# Clock_Distribution.net
KiCad netlist of a schematic drawn in Altium Designer
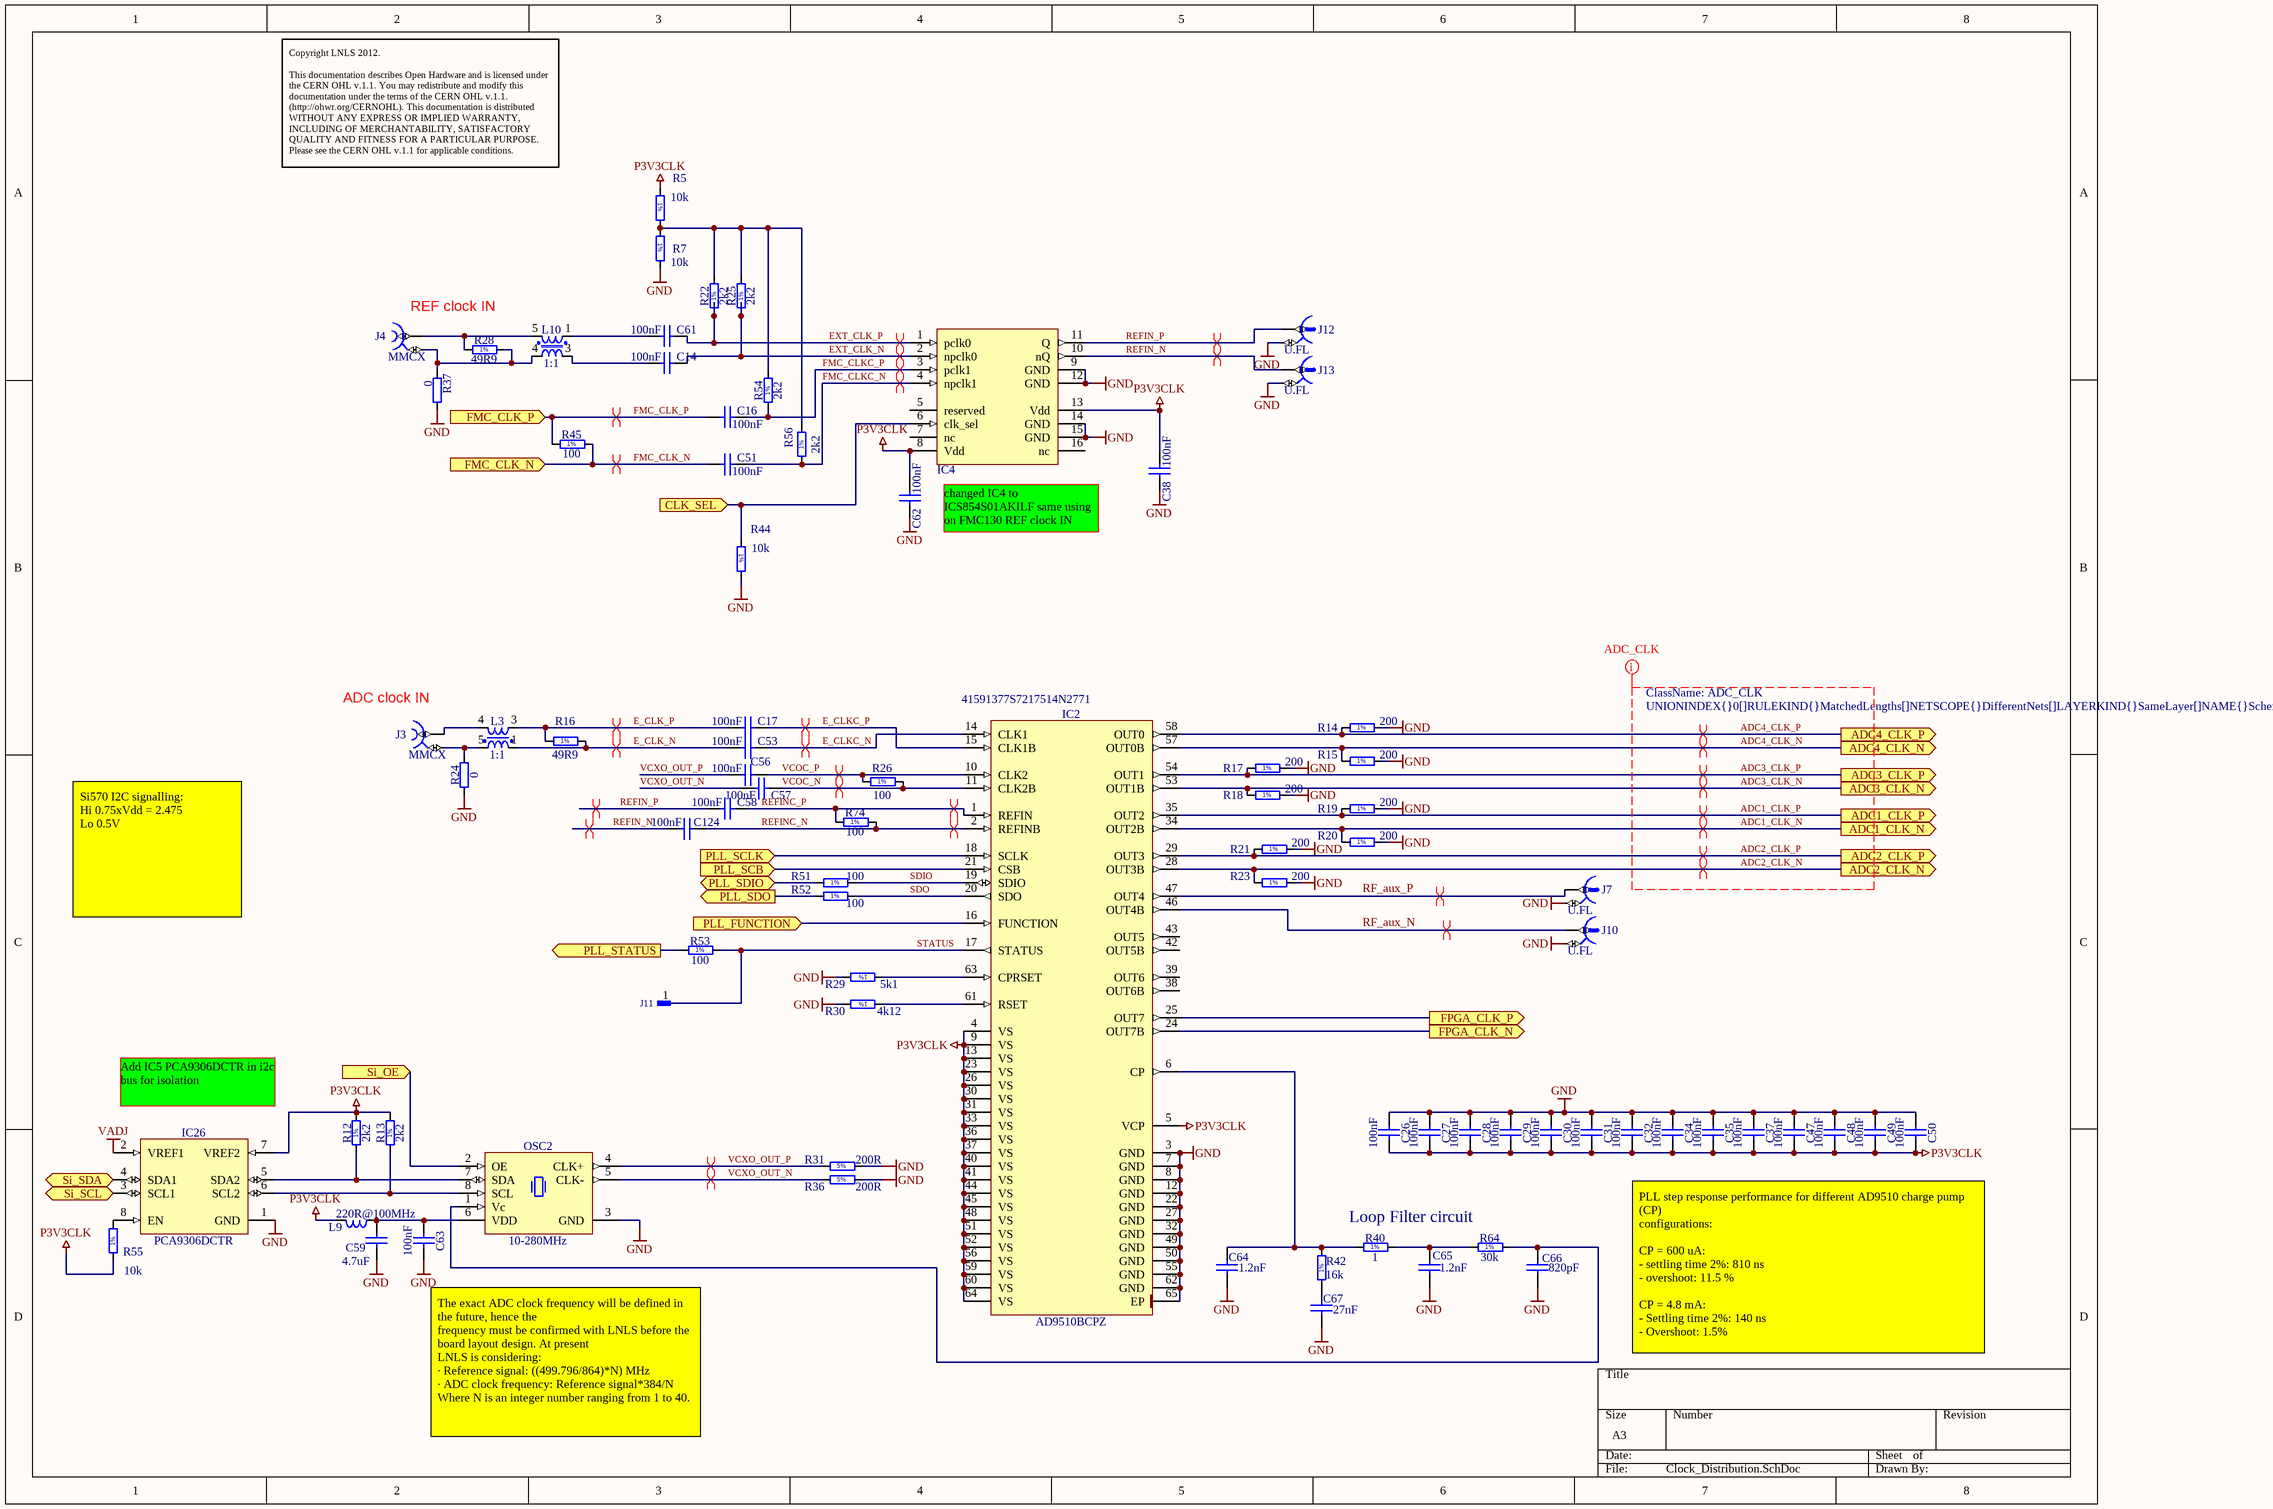
[diagram p0: Clock_Distribution.SchDoc]

(export (version "E")
  (design (tool "Eeschema 10.0.6"))
  (components
    (comp (ref "C14")
      (value "100nF")
      (footprint "CAPC0603X33N")
      (description "Non-polarised capacitor")
      (fields
        (field (name "PART NUMBER") "CC0201_100NF_6.3V_10%_X5R")
        (field (name "VOLTAGE") "6.3V")
        (field (name "AUTHOR") "CERN DEM JLC")
      )
      (libsource (lib "Capacitors") (part "Capacitor - non polarized"))
    )
    (comp (ref "C16")
      (value "100nF")
      (footprint "CAPC0603X33N")
      (description "Non-polarised capacitor")
      (fields
        (field (name "PART NUMBER") "CC0201_100NF_6.3V_10%_X5R")
        (field (name "VOLTAGE") "6.3V")
        (field (name "AUTHOR") "CERN DEM JLC")
      )
      (libsource (lib "Capacitors") (part "Capacitor - non polarized"))
    )
    (comp (ref "C17")
      (value "100nF")
      (footprint "CAPC0603X33N")
      (description "Non-polarised capacitor")
      (fields
        (field (name "PART NUMBER") "CC0201_100NF_6.3V_10%_X5R")
        (field (name "VOLTAGE") "6.3V")
        (field (name "AUTHOR") "CERN DEM JLC")
      )
      (libsource (lib "Capacitors") (part "Capacitor - non polarized"))
    )
    (comp (ref "C26")
      (value "100nF")
      (footprint "CAPC0603X33N")
      (description "Non-polarised capacitor")
      (fields
        (field (name "PART NUMBER") "CC0201_100NF_6.3V_10%_X5R")
        (field (name "VOLTAGE") "6.3V")
        (field (name "AUTHOR") "CERN DEM JLC")
      )
      (libsource (lib "Capacitors") (part "Capacitor - non polarized"))
    )
    (comp (ref "C27")
      (value "100nF")
      (footprint "CAPC0603X33N")
      (description "Non-polarised capacitor")
      (fields
        (field (name "PART NUMBER") "CC0201_100NF_6.3V_10%_X5R")
        (field (name "VOLTAGE") "6.3V")
        (field (name "AUTHOR") "CERN DEM JLC")
      )
      (libsource (lib "Capacitors") (part "Capacitor - non polarized"))
    )
    (comp (ref "C28")
      (value "100nF")
      (footprint "CAPC0603X33N")
      (description "Non-polarised capacitor")
      (fields
        (field (name "PART NUMBER") "CC0201_100NF_6.3V_10%_X5R")
        (field (name "VOLTAGE") "6.3V")
        (field (name "AUTHOR") "CERN DEM JLC")
      )
      (libsource (lib "Capacitors") (part "Capacitor - non polarized"))
    )
    (comp (ref "C29")
      (value "100nF")
      (footprint "CAPC0603X33N")
      (description "Non-polarised capacitor")
      (fields
        (field (name "PART NUMBER") "CC0201_100NF_6.3V_10%_X5R")
        (field (name "VOLTAGE") "6.3V")
        (field (name "AUTHOR") "CERN DEM JLC")
      )
      (libsource (lib "Capacitors") (part "Capacitor - non polarized"))
    )
    (comp (ref "C30")
      (value "100nF")
      (footprint "CAPC0603X33N")
      (description "Non-polarised capacitor")
      (fields
        (field (name "PART NUMBER") "CC0201_100NF_6.3V_10%_X5R")
        (field (name "VOLTAGE") "6.3V")
        (field (name "AUTHOR") "CERN DEM JLC")
      )
      (libsource (lib "Capacitors") (part "Capacitor - non polarized"))
    )
    (comp (ref "C31")
      (value "100nF")
      (footprint "CAPC0603X33N")
      (description "Non-polarised capacitor")
      (fields
        (field (name "PART NUMBER") "CC0201_100NF_6.3V_10%_X5R")
        (field (name "VOLTAGE") "6.3V")
        (field (name "AUTHOR") "CERN DEM JLC")
      )
      (libsource (lib "Capacitors") (part "Capacitor - non polarized"))
    )
    (comp (ref "C32")
      (value "100nF")
      (footprint "CAPC0603X33N")
      (description "Non-polarised capacitor")
      (fields
        (field (name "PART NUMBER") "CC0201_100NF_6.3V_10%_X5R")
        (field (name "VOLTAGE") "6.3V")
        (field (name "AUTHOR") "CERN DEM JLC")
      )
      (libsource (lib "Capacitors") (part "Capacitor - non polarized"))
    )
    (comp (ref "C34")
      (value "100nF")
      (footprint "CAPC0603X33N")
      (description "Non-polarised capacitor")
      (fields
        (field (name "PART NUMBER") "CC0201_100NF_6.3V_10%_X5R")
        (field (name "VOLTAGE") "6.3V")
        (field (name "AUTHOR") "CERN DEM JLC")
      )
      (libsource (lib "Capacitors") (part "Capacitor - non polarized"))
    )
    (comp (ref "C35")
      (value "100nF")
      (footprint "CAPC0603X33N")
      (description "Non-polarised capacitor")
      (fields
        (field (name "PART NUMBER") "CC0201_100NF_6.3V_10%_X5R")
        (field (name "VOLTAGE") "6.3V")
        (field (name "AUTHOR") "CERN DEM JLC")
      )
      (libsource (lib "Capacitors") (part "Capacitor - non polarized"))
    )
    (comp (ref "C37")
      (value "100nF")
      (footprint "CAPC0603X33N")
      (description "Non-polarised capacitor")
      (fields
        (field (name "PART NUMBER") "CC0201_100NF_6.3V_10%_X5R")
        (field (name "VOLTAGE") "6.3V")
        (field (name "AUTHOR") "CERN DEM JLC")
      )
      (libsource (lib "Capacitors") (part "Capacitor - non polarized"))
    )
    (comp (ref "C38")
      (value "100nF")
      (footprint "CAPC0603X33N")
      (description "Non-polarised capacitor")
      (fields
        (field (name "PART NUMBER") "CC0201_100NF_6.3V_10%_X5R")
        (field (name "VOLTAGE") "6.3V")
        (field (name "AUTHOR") "CERN DEM JLC")
      )
      (libsource (lib "Capacitors") (part "Capacitor - non polarized"))
    )
    (comp (ref "C47")
      (value "100nF")
      (footprint "CAPC0603X33N")
      (description "Non-polarised capacitor")
      (fields
        (field (name "PART NUMBER") "CC0201_100NF_6.3V_10%_X5R")
        (field (name "VOLTAGE") "6.3V")
        (field (name "AUTHOR") "CERN DEM JLC")
      )
      (libsource (lib "Capacitors") (part "Capacitor - non polarized"))
    )
    (comp (ref "C48")
      (value "100nF")
      (footprint "CAPC0603X33N")
      (description "Non-polarised capacitor")
      (fields
        (field (name "PART NUMBER") "CC0201_100NF_6.3V_10%_X5R")
        (field (name "VOLTAGE") "6.3V")
        (field (name "AUTHOR") "CERN DEM JLC")
      )
      (libsource (lib "Capacitors") (part "Capacitor - non polarized"))
    )
    (comp (ref "C49")
      (value "100nF")
      (footprint "CAPC0603X33N")
      (description "Non-polarised capacitor")
      (fields
        (field (name "PART NUMBER") "CC0201_100NF_6.3V_10%_X5R")
        (field (name "VOLTAGE") "6.3V")
        (field (name "AUTHOR") "CERN DEM JLC")
      )
      (libsource (lib "Capacitors") (part "Capacitor - non polarized"))
    )
    (comp (ref "C50")
      (value "100nF")
      (footprint "CAPC0603X33N")
      (description "Non-polarised capacitor")
      (fields
        (field (name "PART NUMBER") "CC0201_100NF_6.3V_10%_X5R")
        (field (name "VOLTAGE") "6.3V")
        (field (name "AUTHOR") "CERN DEM JLC")
      )
      (libsource (lib "Capacitors") (part "Capacitor - non polarized"))
    )
    (comp (ref "C51")
      (value "100nF")
      (footprint "CAPC0603X33N")
      (description "Non-polarised capacitor")
      (fields
        (field (name "PART NUMBER") "CC0201_100NF_6.3V_10%_X5R")
        (field (name "VOLTAGE") "6.3V")
        (field (name "AUTHOR") "CERN DEM JLC")
      )
      (libsource (lib "Capacitors") (part "Capacitor - non polarized"))
    )
    (comp (ref "C53")
      (value "100nF")
      (footprint "CAPC0603X33N")
      (description "Non-polarised capacitor")
      (fields
        (field (name "PART NUMBER") "CC0201_100NF_6.3V_10%_X5R")
        (field (name "VOLTAGE") "6.3V")
        (field (name "AUTHOR") "CERN DEM JLC")
      )
      (libsource (lib "Capacitors") (part "Capacitor - non polarized"))
    )
    (comp (ref "C56")
      (value "100nF")
      (footprint "CAPC0603X33N")
      (description "Non-polarised capacitor")
      (fields
        (field (name "PART NUMBER") "CC0201_100NF_6.3V_10%_X5R")
        (field (name "VOLTAGE") "6.3V")
        (field (name "AUTHOR") "CERN DEM JLC")
      )
      (libsource (lib "Capacitors") (part "Capacitor - non polarized"))
    )
    (comp (ref "C57")
      (value "100nF")
      (footprint "CAPC0603X33N")
      (description "Non-polarised capacitor")
      (fields
        (field (name "PART NUMBER") "CC0201_100NF_6.3V_10%_X5R")
        (field (name "VOLTAGE") "6.3V")
        (field (name "AUTHOR") "CERN DEM JLC")
      )
      (libsource (lib "Capacitors") (part "Capacitor - non polarized"))
    )
    (comp (ref "C58")
      (value "100nF")
      (footprint "CAPC0603X33N")
      (description "Non-polarised capacitor")
      (fields
        (field (name "PART NUMBER") "CC0201_100NF_6.3V_10%_X5R")
        (field (name "VOLTAGE") "6.3V")
        (field (name "AUTHOR") "CERN DEM JLC")
      )
      (libsource (lib "Capacitors") (part "Capacitor - non polarized"))
    )
    (comp (ref "C59")
      (value "4.7uF")
      (footprint "CAPC1608X90N")
      (description "Non-polarised capacitor")
      (fields
        (field (name "PART NUMBER") "CC0603_4.7UF_25V_10%_X5R")
        (field (name "VOLTAGE") "25V")
        (field (name "AUTHOR") "CERN DEM JLC")
      )
      (libsource (lib "Capacitors") (part "Capacitor - non polarized"))
    )
    (comp (ref "C61")
      (value "100nF")
      (footprint "CAPC0603X33N")
      (description "Non-polarised capacitor")
      (fields
        (field (name "PART NUMBER") "CC0201_100NF_6.3V_10%_X5R")
        (field (name "VOLTAGE") "6.3V")
        (field (name "AUTHOR") "CERN DEM JLC")
      )
      (libsource (lib "Capacitors") (part "Capacitor - non polarized"))
    )
    (comp (ref "C62")
      (value "100nF")
      (footprint "CAPC0603X33N")
      (description "Non-polarised capacitor")
      (fields
        (field (name "PART NUMBER") "CC0201_100NF_6.3V_10%_X5R")
        (field (name "VOLTAGE") "6.3V")
        (field (name "AUTHOR") "CERN DEM JLC")
      )
      (libsource (lib "Capacitors") (part "Capacitor - non polarized"))
    )
    (comp (ref "C63")
      (value "100nF")
      (footprint "CAPC0603X33N")
      (description "Non-polarised capacitor")
      (fields
        (field (name "PART NUMBER") "CC0201_100NF_6.3V_10%_X5R")
        (field (name "VOLTAGE") "6.3V")
        (field (name "AUTHOR") "CERN DEM JLC")
      )
      (libsource (lib "Capacitors") (part "Capacitor - non polarized"))
    )
    (comp (ref "C64")
      (value "1.2nF")
      (footprint "CAPC1608X87N")
      (description "Non-polarised capacitor")
      (fields
        (field (name "PART NUMBER") "CC0603_1.2NF_50V_10%_X7R")
        (field (name "VOLTAGE") "50V")
        (field (name "AUTHOR") "CERN DEM JLC")
      )
      (libsource (lib "Capacitors") (part "Capacitor - non polarized"))
    )
    (comp (ref "C65")
      (value "1.2nF")
      (footprint "CAPC1608X87N")
      (description "Non-polarised capacitor")
      (fields
        (field (name "PART NUMBER") "CC0603_1.2NF_50V_10%_X7R")
        (field (name "VOLTAGE") "50V")
        (field (name "AUTHOR") "CERN DEM JLC")
      )
      (libsource (lib "Capacitors") (part "Capacitor - non polarized"))
    )
    (comp (ref "C66")
      (value "820pF")
      (footprint "CAPC1608X87N")
      (description "Non-polarised capacitor")
      (fields
        (field (name "PART NUMBER") "CC0603_820PF_50V_10%_X7R")
        (field (name "VOLTAGE") "50V")
        (field (name "AUTHOR") "CERN DEM JLC")
      )
      (libsource (lib "Capacitors") (part "Capacitor - non polarized"))
    )
    (comp (ref "C67")
      (value "27nF")
      (footprint "CAPC1608X87N")
      (description "Non-polarised capacitor")
      (fields
        (field (name "PART NUMBER") "CC0603_27NF_25V_10%_X7R")
        (field (name "VOLTAGE") "25V")
        (field (name "AUTHOR") "CERN DEM JLC")
      )
      (libsource (lib "Capacitors") (part "Capacitor - non polarized"))
    )
    (comp (ref "C124")
      (value "100nF")
      (footprint "CAPC0603X33N")
      (description "Non-polarised capacitor")
      (fields
        (field (name "PART NUMBER") "CC0201_100NF_6.3V_10%_X5R")
        (field (name "VOLTAGE") "6.3V")
        (field (name "AUTHOR") "CERN DEM JLC")
      )
      (libsource (lib "Capacitors") (part "Capacitor - non polarized"))
    )
    (comp (ref "IC2")
      (value "AD9510BCPZ")
      (footprint "QFN50P900X900X100-65N-S485")
      (description "1.2 GHz Clock Distribution IC, PLL Core, Dividers, Delay Adjust, Eight Outputs")
      (fields
        (field (name "MANUFACTURER") "ANALOG DEVICES")
        (field (name "SUPPLIER PART NUMBER 1") "41591377S7217514N2771")
        (field (name "AUTHOR") "CERN DEM JLC")
      )
      (libsource (lib "ICs And Semiconductors") (part "AD9510"))
    )
    (comp (ref "IC4")
      (value "ICS854S01AKILF")
      (footprint "QFN50P300x300x100-17N-S140")
      (description "2:1 Differential-to-LVDS Multiplexer")
      (fields
        (field (name "MANUFACTURER") "INTEGRATED DEVICE TECHNOLOGY (IDT)")
        (field (name "AUTHOR") "LNLS DIG GBMB")
      )
      (libsource (lib "ICs And Semiconductors_LNLS") (part "ICS854S01l"))
    )
    (comp (ref "IC26")
      (value "PCA9306DCTR")
      (footprint "SOP65P400X130-8N")
      (description "Dual Bidirectional I2C Bus And SMBus Voltage-Level Translator")
      (fields (field (name "MANUFACTURER") "TEXAS INSTRUMENTS") (field (name "AUTHOR") "CERN DEM JLC"))
      (libsource (lib "ICs And Semiconductors") (part "PCA9306DC"))
    )
    (comp (ref "J3")
      (value "MMCX")
      (footprint "HUBER-SUHNER_85_MMCX-50-0-1/111_OH")
      (fields
        (field (name "PART NUMBER") "HUBER-SUHNER_85_MMCX-50-0-1/111_OH")
        (field (name "MANUFACTURER") "HUBER+SUHNER")
        (field (name "MANUFACTURER PART NUMBER") "85_MMCX-50-0-1/111_OH")
        (field (name "AUTHOR") "CERN DEM JLC")
      )
      (libsource (lib "Connectors") (part "Coax_1Female_1Shield"))
    )
    (comp (ref "J4")
      (value "MMCX")
      (footprint "HUBER-SUHNER_85_MMCX-50-0-1/111_OH")
      (fields
        (field (name "PART NUMBER") "HUBER-SUHNER_85_MMCX-50-0-1/111_OH")
        (field (name "MANUFACTURER") "HUBER+SUHNER")
        (field (name "MANUFACTURER PART NUMBER") "85_MMCX-50-0-1/111_OH")
        (field (name "AUTHOR") "CERN DEM JLC")
      )
      (libsource (lib "Connectors") (part "Coax_1Female_1Shield"))
    )
    (comp (ref "J7")
      (value "U.FL")
      (footprint "HIROSE_U.FL-R-SMT-1(10)")
      (fields
        (field (name "PART NUMBER") "HIROSE_U.FL-R-SMT-1(10)")
        (field (name "MANUFACTURER") "HIROSE (HRS)")
        (field (name "MANUFACTURER PART NUMBER") "U.FL-R-SMT-1(10)")
        (field (name "AUTHOR") "CERN DEM JLC")
      )
      (libsource (lib "Connectors") (part "Coax_1Male_1Shield"))
    )
    (comp (ref "J10")
      (value "U.FL")
      (footprint "HIROSE_U.FL-R-SMT-1(10)")
      (fields
        (field (name "PART NUMBER") "HIROSE_U.FL-R-SMT-1(10)")
        (field (name "MANUFACTURER") "HIROSE (HRS)")
        (field (name "MANUFACTURER PART NUMBER") "U.FL-R-SMT-1(10)")
        (field (name "AUTHOR") "CERN DEM JLC")
      )
      (libsource (lib "Connectors") (part "Coax_1Male_1Shield"))
    )
    (comp (ref "J11")
      (value "SMD Pad")
      (footprint "R400X300")
      (description "Single SMD Pad")
      (fields (field (name "PART NUMBER") "SMD_PAD_4X3MM") (field (name "AUTHOR") "CERN DEM JLC"))
      (libsource (lib "Eletro-mechanical") (part "Single SMD Pad"))
    )
    (comp (ref "J12")
      (value "U.FL")
      (footprint "HIROSE_U.FL-R-SMT-1(10)")
      (fields
        (field (name "PART NUMBER") "HIROSE_U.FL-R-SMT-1(10)")
        (field (name "MANUFACTURER") "HIROSE (HRS)")
        (field (name "MANUFACTURER PART NUMBER") "U.FL-R-SMT-1(10)")
        (field (name "AUTHOR") "CERN DEM JLC")
      )
      (libsource (lib "Connectors") (part "Coax_1Male_1Shield"))
    )
    (comp (ref "J13")
      (value "U.FL")
      (footprint "HIROSE_U.FL-R-SMT-1(10)")
      (fields
        (field (name "PART NUMBER") "HIROSE_U.FL-R-SMT-1(10)")
        (field (name "MANUFACTURER") "HIROSE (HRS)")
        (field (name "MANUFACTURER PART NUMBER") "U.FL-R-SMT-1(10)")
        (field (name "AUTHOR") "CERN DEM JLC")
      )
      (libsource (lib "Connectors") (part "Coax_1Male_1Shield"))
    )
    (comp (ref "L3")
      (value "1:1")
      (footprint "XFMR_MA-COM_SM-22 (H260)")
      (description "MA-COM E-Serie RF 1:1 Transmission Line Ttransformer 4.5-3000MHz")
      (fields
        (field (name "PART NUMBER") "XFMR_MA-COM_MABA-007159-000000")
        (field (name "MANUFACTURER") "MA-COM TECHNOLOGY")
        (field (name "AUTHOR") "CERN DEM JLC")
      )
      (libsource (lib "Inductors & Transformers") (part "XFMR_MA-COM_MABA-007159-000000"))
    )
    (comp (ref "L9")
      (value "220R@100MHz")
      (footprint "INDC1005X55N")
      (description "Inductor")
      (fields
        (field (name "PART NUMBER") "IND0402_MURATA_BLM15HB221SN1")
        (field (name "POWER") "250mA")
        (field (name "AUTHOR") "CERN DEM JLC")
      )
      (libsource (lib "Inductors & Transformers") (part "Inductor"))
    )
    (comp (ref "L10")
      (value "1:1")
      (footprint "XFMR_MA-COM_SM-22 (H260)")
      (description "MA-COM E-Serie RF 1:1 Transmission Line Ttransformer 4.5-3000MHz")
      (fields
        (field (name "PART NUMBER") "XFMR_MA-COM_MABA-007159-000000")
        (field (name "MANUFACTURER") "MA-COM TECHNOLOGY")
        (field (name "AUTHOR") "CERN DEM JLC")
      )
      (libsource (lib "") (part "XFMR_MA-COM_MABA-007159-000000_1"))
    )
    (comp (ref "OSC2")
      (value "10-280MHz")
      (footprint "OSC_SILICON-LAB_SI571")
      (description "Any-Rate I2C Programmable XO Oscillator Si571 Serie")
      (fields
        (field (name "PART NUMBER") "OSC_10-280MHZ_SILICON-LAB_Si571AJC000337DG")
        (field (name "MANUFACTURER") "SILICON LABS")
        (field (name "AUTHOR") "CERN DEM JLC")
      )
      (libsource (lib "ICs And Semiconductors") (part "Oscillator SILICON-LAB_Si571"))
    )
    (comp (ref "R5")
      (value "10k")
      (footprint "RESC1005X40N")
      (description "Resistor - 1%")
      (fields
        (field (name "PART NUMBER") "R0402_10K_1%_0.0625W_100PPM")
        (field (name "POWER") "0.0625W")
        (field (name "AUTHOR") "CERN DEM JLC")
      )
      (libsource (lib "Resistors") (part "Resistor - 1%"))
    )
    (comp (ref "R7")
      (value "10k")
      (footprint "RESC1005X40N")
      (description "Resistor - 1%")
      (fields
        (field (name "PART NUMBER") "R0402_10K_1%_0.0625W_100PPM")
        (field (name "POWER") "0.0625W")
        (field (name "AUTHOR") "CERN DEM JLC")
      )
      (libsource (lib "Resistors") (part "Resistor - 1%"))
    )
    (comp (ref "R12")
      (value "2k2")
      (footprint "RESC1005X40N")
      (description "Resistor - 1%")
      (fields
        (field (name "PART NUMBER") "R0402_2K2_1%_0.0625W_100PPM")
        (field (name "POWER") "0.0625W")
        (field (name "AUTHOR") "CERN DEM JLC")
      )
      (libsource (lib "Resistors") (part "Resistor - 1%"))
    )
    (comp (ref "R13")
      (value "2k2")
      (footprint "RESC1005X40N")
      (description "Resistor - 1%")
      (fields
        (field (name "PART NUMBER") "R0402_2K2_1%_0.0625W_100PPM")
        (field (name "POWER") "0.0625W")
        (field (name "AUTHOR") "CERN DEM JLC")
      )
      (libsource (lib "Resistors") (part "Resistor - 1%"))
    )
    (comp (ref "R14")
      (value "200")
      (footprint "RESC1005X40N")
      (description "Resistor - 1%")
      (fields
        (field (name "PART NUMBER") "R0402_200R_1%_0.0625W_100PPM")
        (field (name "POWER") "0.0625W")
        (field (name "AUTHOR") "CERN DEM JLC")
      )
      (libsource (lib "Resistors") (part "Resistor - 1%"))
    )
    (comp (ref "R15")
      (value "200")
      (footprint "RESC1005X40N")
      (description "Resistor - 1%")
      (fields
        (field (name "PART NUMBER") "R0402_200R_1%_0.0625W_100PPM")
        (field (name "POWER") "0.0625W")
        (field (name "AUTHOR") "CERN DEM JLC")
      )
      (libsource (lib "Resistors") (part "Resistor - 1%"))
    )
    (comp (ref "R16")
      (value "49R9")
      (footprint "RESC1005X40N")
      (description "Resistor - 1%")
      (fields
        (field (name "PART NUMBER") "R0402_49R9_1%_0.0625W_100PPM")
        (field (name "POWER") "0.0625W")
        (field (name "AUTHOR") "CERN DEM JLC")
      )
      (libsource (lib "Resistors") (part "Resistor - 1%"))
    )
    (comp (ref "R17")
      (value "200")
      (footprint "RESC1005X40N")
      (description "Resistor - 1%")
      (fields
        (field (name "PART NUMBER") "R0402_200R_1%_0.0625W_100PPM")
        (field (name "POWER") "0.0625W")
        (field (name "AUTHOR") "CERN DEM JLC")
      )
      (libsource (lib "Resistors") (part "Resistor - 1%"))
    )
    (comp (ref "R18")
      (value "200")
      (footprint "RESC1005X40N")
      (description "Resistor - 1%")
      (fields
        (field (name "PART NUMBER") "R0402_200R_1%_0.0625W_100PPM")
        (field (name "POWER") "0.0625W")
        (field (name "AUTHOR") "CERN DEM JLC")
      )
      (libsource (lib "Resistors") (part "Resistor - 1%"))
    )
    (comp (ref "R19")
      (value "200")
      (footprint "RESC1005X40N")
      (description "Resistor - 1%")
      (fields
        (field (name "PART NUMBER") "R0402_200R_1%_0.0625W_100PPM")
        (field (name "POWER") "0.0625W")
        (field (name "AUTHOR") "CERN DEM JLC")
      )
      (libsource (lib "Resistors") (part "Resistor - 1%"))
    )
    (comp (ref "R20")
      (value "200")
      (footprint "RESC1005X40N")
      (description "Resistor - 1%")
      (fields
        (field (name "PART NUMBER") "R0402_200R_1%_0.0625W_100PPM")
        (field (name "POWER") "0.0625W")
        (field (name "AUTHOR") "CERN DEM JLC")
      )
      (libsource (lib "Resistors") (part "Resistor - 1%"))
    )
    (comp (ref "R21")
      (value "200")
      (footprint "RESC1005X40N")
      (description "Resistor - 1%")
      (fields
        (field (name "PART NUMBER") "R0402_200R_1%_0.0625W_100PPM")
        (field (name "POWER") "0.0625W")
        (field (name "AUTHOR") "CERN DEM JLC")
      )
      (libsource (lib "Resistors") (part "Resistor - 1%"))
    )
    (comp (ref "R22")
      (value "2k2")
      (footprint "RESC1005X40N")
      (description "Resistor - 1%")
      (fields
        (field (name "PART NUMBER") "R0402_2K2_1%_0.0625W_100PPM")
        (field (name "POWER") "0.0625W")
        (field (name "AUTHOR") "CERN DEM JLC")
      )
      (libsource (lib "Resistors") (part "Resistor - 1%"))
    )
    (comp (ref "R23")
      (value "200")
      (footprint "RESC1005X40N")
      (description "Resistor - 1%")
      (fields
        (field (name "PART NUMBER") "R0402_200R_1%_0.0625W_100PPM")
        (field (name "POWER") "0.0625W")
        (field (name "AUTHOR") "CERN DEM JLC")
      )
      (libsource (lib "Resistors") (part "Resistor - 1%"))
    )
    (comp (ref "R24")
      (value "0")
      (footprint "RESC0603X28N")
      (description "Resistor")
      (fields
        (field (name "PART NUMBER") "R0201_0R_JUMPER")
        (field (name "MANUFACTURER") "GENERIC")
        (field (name "AUTHOR") "CERN DEM JLC")
      )
      (libsource (lib "Resistors") (part "Resistor"))
    )
    (comp (ref "R25")
      (value "2k2")
      (footprint "RESC1005X40N")
      (description "Resistor - 1%")
      (fields
        (field (name "PART NUMBER") "R0402_2K2_1%_0.0625W_100PPM")
        (field (name "POWER") "0.0625W")
        (field (name "AUTHOR") "CERN DEM JLC")
      )
      (libsource (lib "Resistors") (part "Resistor - 1%"))
    )
    (comp (ref "R26")
      (value "100")
      (footprint "RESC1005X40N")
      (description "Resistor - 1%")
      (fields
        (field (name "PART NUMBER") "R0402_100R_1%_0.0625W_100PPM")
        (field (name "POWER") "0.0625W")
        (field (name "AUTHOR") "CERN DEM JLC")
      )
      (libsource (lib "Resistors") (part "Resistor - 1%"))
    )
    (comp (ref "R28")
      (value "49R9")
      (footprint "RESC1005X40N")
      (description "Resistor - 1%")
      (fields
        (field (name "PART NUMBER") "R0402_49R9_1%_0.0625W_100PPM")
        (field (name "POWER") "0.0625W")
        (field (name "AUTHOR") "CERN DEM JLC")
      )
      (libsource (lib "Resistors") (part "Resistor - 1%"))
    )
    (comp (ref "R29")
      (value "5k1")
      (footprint "RESC1005X40N")
      (description "Resistor - 1%")
      (fields
        (field (name "PART NUMBER") "R0402_5K1_1%_0.0625W_100PPM")
        (field (name "POWER") "0.0625W")
        (field (name "AUTHOR") "CERN DEM JLC")
      )
      (libsource (lib "Resistors") (part "Resistor - 1%"))
    )
    (comp (ref "R30")
      (value "4k12")
      (footprint "RESC1005X40N")
      (description "Resistor - 1%")
      (fields
        (field (name "PART NUMBER") "R0402_4K12_1%_0.0625W_100PPM")
        (field (name "POWER") "0.0625W")
        (field (name "AUTHOR") "CERN DEM JLC")
      )
      (libsource (lib "Resistors") (part "Resistor - 1%"))
    )
    (comp (ref "R31")
      (value "200R")
      (footprint "RESC1005X40N")
      (description "Resistor - 5%")
      (fields
        (field (name "PART NUMBER") "R0402_200R_5%_0.0625W_100PPM")
        (field (name "TOLERANCE") "5%")
        (field (name "AUTHOR") "CERN DEM JLC")
      )
      (libsource (lib "Resistors") (part "Resistor - 5%"))
    )
    (comp (ref "R36")
      (value "200R")
      (footprint "RESC1005X40N")
      (description "Resistor - 5%")
      (fields
        (field (name "PART NUMBER") "R0402_200R_5%_0.0625W_100PPM")
        (field (name "TOLERANCE") "5%")
        (field (name "AUTHOR") "CERN DEM JLC")
      )
      (libsource (lib "Resistors") (part "Resistor - 5%"))
    )
    (comp (ref "R37")
      (value "0")
      (footprint "RESC0603X28N")
      (description "Resistor")
      (fields
        (field (name "PART NUMBER") "R0201_0R_JUMPER")
        (field (name "MANUFACTURER") "GENERIC")
        (field (name "AUTHOR") "CERN DEM JLC")
      )
      (libsource (lib "Resistors") (part "Resistor"))
    )
    (comp (ref "R40")
      (value "1")
      (footprint "RESC1005X40N")
      (description "Resistor - 1%")
      (fields
        (field (name "PART NUMBER") "R0402_1R_1%_0.0625W_200PPM")
        (field (name "POWER") "0.0625W")
        (field (name "AUTHOR") "CERN DEM JLC")
      )
      (libsource (lib "Resistors") (part "Resistor - 1%"))
    )
    (comp (ref "R42")
      (value "16k")
      (footprint "RESC1608X55N")
      (description "Resistor - 1%")
      (fields
        (field (name "PART NUMBER") "R0603_16K_1%_0.1W_100PPM")
        (field (name "POWER") "0.1W")
        (field (name "AUTHOR") "CERN DEM JLC")
      )
      (libsource (lib "Resistors") (part "Resistor - 1%"))
    )
    (comp (ref "R44")
      (value "10k")
      (footprint "RESC1005X40N")
      (description "Resistor - 1%")
      (fields
        (field (name "PART NUMBER") "R0402_10K_1%_0.0625W_100PPM")
        (field (name "POWER") "0.0625W")
        (field (name "AUTHOR") "CERN DEM JLC")
      )
      (libsource (lib "Resistors") (part "Resistor - 1%"))
    )
    (comp (ref "R45")
      (value "100")
      (footprint "RESC1005X40N")
      (description "Resistor - 1%")
      (fields
        (field (name "PART NUMBER") "R0402_100R_1%_0.0625W_100PPM")
        (field (name "POWER") "0.0625W")
        (field (name "AUTHOR") "CERN DEM JLC")
      )
      (libsource (lib "Resistors") (part "Resistor - 1%"))
    )
    (comp (ref "R51")
      (value "100")
      (footprint "RESC1005X40N")
      (description "Resistor - 1%")
      (fields
        (field (name "PART NUMBER") "R0402_100R_1%_0.0625W_100PPM")
        (field (name "POWER") "0.0625W")
        (field (name "AUTHOR") "CERN DEM JLC")
      )
      (libsource (lib "Resistors") (part "Resistor - 1%"))
    )
    (comp (ref "R52")
      (value "100")
      (footprint "RESC1005X40N")
      (description "Resistor - 1%")
      (fields
        (field (name "PART NUMBER") "R0402_100R_1%_0.0625W_100PPM")
        (field (name "POWER") "0.0625W")
        (field (name "AUTHOR") "CERN DEM JLC")
      )
      (libsource (lib "Resistors") (part "Resistor - 1%"))
    )
    (comp (ref "R53")
      (value "100")
      (footprint "RESC1005X40N")
      (description "Resistor - 1%")
      (fields
        (field (name "PART NUMBER") "R0402_100R_1%_0.0625W_100PPM")
        (field (name "POWER") "0.0625W")
        (field (name "AUTHOR") "CERN DEM JLC")
      )
      (libsource (lib "Resistors") (part "Resistor - 1%"))
    )
    (comp (ref "R54")
      (value "2k2")
      (footprint "RESC1005X40N")
      (description "Resistor - 1%")
      (fields
        (field (name "PART NUMBER") "R0402_2K2_1%_0.0625W_100PPM")
        (field (name "POWER") "0.0625W")
        (field (name "AUTHOR") "CERN DEM JLC")
      )
      (libsource (lib "Resistors") (part "Resistor - 1%"))
    )
    (comp (ref "R55")
      (value "10k")
      (footprint "RESC1005X40N")
      (description "Resistor - 1%")
      (fields
        (field (name "PART NUMBER") "R0402_10K_1%_0.0625W_100PPM")
        (field (name "POWER") "0.0625W")
        (field (name "AUTHOR") "CERN DEM JLC")
      )
      (libsource (lib "Resistors") (part "Resistor - 1%"))
    )
    (comp (ref "R56")
      (value "2k2")
      (footprint "RESC1005X40N")
      (description "Resistor - 1%")
      (fields
        (field (name "PART NUMBER") "R0402_2K2_1%_0.0625W_100PPM")
        (field (name "POWER") "0.0625W")
        (field (name "AUTHOR") "CERN DEM JLC")
      )
      (libsource (lib "Resistors") (part "Resistor - 1%"))
    )
    (comp (ref "R64")
      (value "30k")
      (footprint "RESC1608X55N")
      (description "Resistor - 1%")
      (fields
        (field (name "PART NUMBER") "R0603_30K_1%_0.1W_100PPM")
        (field (name "POWER") "0.1W")
        (field (name "AUTHOR") "CERN DEM JLC")
      )
      (libsource (lib "Resistors") (part "Resistor - 1%"))
    )
    (comp (ref "R74")
      (value "100")
      (footprint "RESC1005X40N")
      (description "Resistor - 1%")
      (fields
        (field (name "PART NUMBER") "R0402_100R_1%_0.0625W_100PPM")
        (field (name "POWER") "0.0625W")
        (field (name "AUTHOR") "CERN DEM JLC")
      )
      (libsource (lib "Resistors") (part "Resistor - 1%"))
    )
  )
  (nets
    (net (code "1") (name "/ADC1_CLK_N") (class "Default")
      (node (ref "IC2") (pin "34") (pinfunction "OUT2B_34") (pintype "output"))
      (node (ref "R20") (pin "1") (pinfunction "1_1") (pintype "passive"))
    )
    (net (code "2") (name "/ADC1_CLK_P") (class "Default")
      (node (ref "IC2") (pin "35") (pinfunction "OUT2_35") (pintype "output"))
      (node (ref "R19") (pin "1") (pinfunction "1_1") (pintype "passive"))
    )
    (net (code "3") (name "/ADC2_CLK_N") (class "Default")
      (node (ref "IC2") (pin "28") (pinfunction "OUT3B_28") (pintype "output"))
      (node (ref "R23") (pin "1") (pinfunction "1_1") (pintype "passive"))
    )
    (net (code "4") (name "/ADC2_CLK_P") (class "Default")
      (node (ref "IC2") (pin "29") (pinfunction "OUT3_29") (pintype "output"))
      (node (ref "R21") (pin "1") (pinfunction "1_1") (pintype "passive"))
    )
    (net (code "5") (name "/ADC3_CLK_N") (class "Default")
      (node (ref "IC2") (pin "53") (pinfunction "OUT1B_53") (pintype "output"))
      (node (ref "R18") (pin "1") (pinfunction "1_1") (pintype "passive"))
    )
    (net (code "6") (name "/ADC3_CLK_P") (class "Default")
      (node (ref "IC2") (pin "54") (pinfunction "OUT1_54") (pintype "output"))
      (node (ref "R17") (pin "1") (pinfunction "1_1") (pintype "passive"))
    )
    (net (code "7") (name "/ADC4_CLK_N") (class "Default")
      (node (ref "IC2") (pin "57") (pinfunction "OUT0B_57") (pintype "output"))
      (node (ref "R15") (pin "1") (pinfunction "1_1") (pintype "passive"))
    )
    (net (code "8") (name "/ADC4_CLK_P") (class "Default")
      (node (ref "IC2") (pin "58") (pinfunction "OUT0_58") (pintype "output"))
      (node (ref "R14") (pin "1") (pinfunction "1_1") (pintype "passive"))
    )
    (net (code "9") (name "/CLK_SEL") (class "Default")
      (node (ref "IC4") (pin "6") (pinfunction "clk_sel_6") (pintype "input"))
      (node (ref "R44") (pin "1") (pinfunction "1_1") (pintype "passive"))
    )
    (net (code "10") (name "/EXT_CLK_N") (class "Default")
      (node (ref "C14") (pin "1") (pinfunction "1_1") (pintype "passive"))
      (node (ref "IC4") (pin "2") (pinfunction "npclk0_2") (pintype "input"))
      (node (ref "R25") (pin "1") (pinfunction "1_1") (pintype "passive"))
    )
    (net (code "11") (name "/EXT_CLK_P") (class "Default")
      (node (ref "C61") (pin "1") (pinfunction "1_1") (pintype "passive"))
      (node (ref "IC4") (pin "1") (pinfunction "pclk0_1") (pintype "input"))
      (node (ref "R22") (pin "1") (pinfunction "1_1") (pintype "passive"))
    )
    (net (code "12") (name "/E_CLKC_N") (class "Default")
      (node (ref "C53") (pin "1") (pinfunction "1_1") (pintype "passive"))
      (node (ref "IC2") (pin "14") (pinfunction "CLK1_14") (pintype "input"))
    )
    (net (code "13") (name "/E_CLKC_P") (class "Default")
      (node (ref "C17") (pin "1") (pinfunction "1_1") (pintype "passive"))
      (node (ref "IC2") (pin "15") (pinfunction "CLK1B_15") (pintype "input"))
    )
    (net (code "14") (name "/E_CLK_N") (class "Default")
      (node (ref "C53") (pin "2") (pinfunction "2_2") (pintype "passive"))
      (node (ref "L3") (pin "1") (pinfunction "1_1") (pintype "passive"))
      (node (ref "R16") (pin "2") (pinfunction "2_2") (pintype "passive"))
    )
    (net (code "15") (name "/E_CLK_P") (class "Default")
      (node (ref "C17") (pin "2") (pinfunction "2_2") (pintype "passive"))
      (node (ref "L3") (pin "3") (pinfunction "3_3") (pintype "passive"))
      (node (ref "R16") (pin "1") (pinfunction "1_1") (pintype "passive"))
    )
    (net (code "16") (name "/FMC_CLKC_N") (class "Default")
      (node (ref "C51") (pin "1") (pinfunction "1_1") (pintype "passive"))
      (node (ref "IC4") (pin "4") (pinfunction "npclk1_4") (pintype "input"))
      (node (ref "R56") (pin "1") (pinfunction "1_1") (pintype "passive"))
    )
    (net (code "17") (name "/FMC_CLKC_P") (class "Default")
      (node (ref "C16") (pin "1") (pinfunction "1_1") (pintype "passive"))
      (node (ref "IC4") (pin "3") (pinfunction "pclk1_3") (pintype "input"))
      (node (ref "R54") (pin "1") (pinfunction "1_1") (pintype "passive"))
    )
    (net (code "18") (name "/FMC_CLK_N") (class "Default")
      (node (ref "C51") (pin "2") (pinfunction "2_2") (pintype "passive"))
      (node (ref "R45") (pin "2") (pinfunction "2_2") (pintype "passive"))
    )
    (net (code "19") (name "/FMC_CLK_P") (class "Default")
      (node (ref "C16") (pin "2") (pinfunction "2_2") (pintype "passive"))
      (node (ref "R45") (pin "1") (pinfunction "1_1") (pintype "passive"))
    )
    (net (code "20") (name "/FPGA_CLK_N") (class "Default")
      (node (ref "IC2") (pin "24") (pinfunction "OUT7B_24") (pintype "output"))
    )
    (net (code "21") (name "/FPGA_CLK_P") (class "Default")
      (node (ref "IC2") (pin "25") (pinfunction "OUT7_25") (pintype "output"))
    )
    (net (code "22") (name "/PLL_FUNCTION") (class "Default")
      (node (ref "IC2") (pin "16") (pinfunction "FUNCTION_16") (pintype "input"))
    )
    (net (code "23") (name "/PLL_SCB") (class "Default")
      (node (ref "IC2") (pin "21") (pinfunction "CSB_21") (pintype "input"))
    )
    (net (code "24") (name "/PLL_SCLK") (class "Default")
      (node (ref "IC2") (pin "18") (pinfunction "SCLK_18") (pintype "input"))
    )
    (net (code "25") (name "/PLL_SDIO") (class "Default")
      (node (ref "R51") (pin "1") (pinfunction "1_1") (pintype "passive"))
    )
    (net (code "26") (name "/PLL_SDO") (class "Default")
      (node (ref "R52") (pin "1") (pinfunction "1_1") (pintype "passive"))
    )
    (net (code "27") (name "/PLL_STATUS") (class "Default")
      (node (ref "R53") (pin "1") (pinfunction "1_1") (pintype "passive"))
    )
    (net (code "28") (name "/REFINC_N") (class "Default")
      (node (ref "C124") (pin "1") (pinfunction "1_1") (pintype "passive"))
      (node (ref "IC2") (pin "2") (pinfunction "REFINB_2") (pintype "input"))
      (node (ref "R74") (pin "2") (pinfunction "2_2") (pintype "passive"))
    )
    (net (code "29") (name "/REFINC_P") (class "Default")
      (node (ref "C58") (pin "1") (pinfunction "1_1") (pintype "passive"))
      (node (ref "IC2") (pin "1") (pinfunction "REFIN_1") (pintype "input"))
      (node (ref "R74") (pin "1") (pinfunction "1_1") (pintype "passive"))
    )
    (net (code "30") (name "/REFIN_N") (class "Default")
      (node (ref "C124") (pin "2") (pinfunction "2_2") (pintype "passive"))
      (node (ref "IC4") (pin "10") (pinfunction "nQ_10") (pintype "output"))
      (node (ref "J13") (pin "1") (pinfunction "1_1") (pintype "bidirectional"))
    )
    (net (code "31") (name "/REFIN_P") (class "Default")
      (node (ref "C58") (pin "2") (pinfunction "2_2") (pintype "passive"))
      (node (ref "IC4") (pin "11") (pinfunction "Q_11") (pintype "output"))
      (node (ref "J12") (pin "1") (pinfunction "1_1") (pintype "bidirectional"))
    )
    (net (code "32") (name "/RF_aux_N") (class "Default")
      (node (ref "IC2") (pin "46") (pinfunction "OUT4B_46") (pintype "output"))
      (node (ref "J10") (pin "1") (pinfunction "1_1") (pintype "bidirectional"))
    )
    (net (code "33") (name "/RF_aux_P") (class "Default")
      (node (ref "IC2") (pin "47") (pinfunction "OUT4_47") (pintype "output"))
      (node (ref "J7") (pin "1") (pinfunction "1_1") (pintype "bidirectional"))
    )
    (net (code "34") (name "/SDIO") (class "Default")
      (node (ref "IC2") (pin "19") (pinfunction "SDIO_19") (pintype "bidirectional"))
      (node (ref "R51") (pin "2") (pinfunction "2_2") (pintype "passive"))
    )
    (net (code "35") (name "/SDO") (class "Default")
      (node (ref "IC2") (pin "20") (pinfunction "SDO_20") (pintype "output"))
      (node (ref "R52") (pin "2") (pinfunction "2_2") (pintype "passive"))
    )
    (net (code "36") (name "/STATUS") (class "Default")
      (node (ref "IC2") (pin "17") (pinfunction "STATUS_17") (pintype "output"))
      (node (ref "J11") (pin "1") (pinfunction "1_1") (pintype "bidirectional"))
      (node (ref "R53") (pin "2") (pinfunction "2_2") (pintype "passive"))
    )
    (net (code "37") (name "/Si_OE") (class "Default")
      (node (ref "OSC2") (pin "2") (pinfunction "OE_2") (pintype "input"))
    )
    (net (code "38") (name "/Si_SCL") (class "Default")
      (node (ref "IC26") (pin "3") (pinfunction "SCL1_3") (pintype "bidirectional"))
    )
    (net (code "39") (name "/Si_SDA") (class "Default")
      (node (ref "IC26") (pin "4") (pinfunction "SDA1_4") (pintype "bidirectional"))
    )
    (net (code "40") (name "/VCOC_N") (class "Default")
      (node (ref "C57") (pin "1") (pinfunction "1_1") (pintype "passive"))
      (node (ref "IC2") (pin "11") (pinfunction "CLK2B_11") (pintype "input"))
      (node (ref "R26") (pin "2") (pinfunction "2_2") (pintype "passive"))
    )
    (net (code "41") (name "/VCOC_P") (class "Default")
      (node (ref "C56") (pin "1") (pinfunction "1_1") (pintype "passive"))
      (node (ref "IC2") (pin "10") (pinfunction "CLK2_10") (pintype "input"))
      (node (ref "R26") (pin "1") (pinfunction "1_1") (pintype "passive"))
    )
    (net (code "42") (name "/VCXO_OUT_N") (class "Default")
      (node (ref "C57") (pin "2") (pinfunction "2_2") (pintype "passive"))
      (node (ref "OSC2") (pin "5") (pinfunction "CLK-_5") (pintype "output"))
      (node (ref "R36") (pin "1") (pinfunction "1_1") (pintype "passive"))
    )
    (net (code "43") (name "/VCXO_OUT_P") (class "Default")
      (node (ref "C56") (pin "2") (pinfunction "2_2") (pintype "passive"))
      (node (ref "OSC2") (pin "4") (pinfunction "CLK+_4") (pintype "output"))
      (node (ref "R31") (pin "1") (pinfunction "1_1") (pintype "passive"))
    )
    (net (code "44") (name "GND") (class "Default")
      (node (ref "C26") (pin "1") (pinfunction "1_1") (pintype "passive"))
      (node (ref "C27") (pin "1") (pinfunction "1_1") (pintype "passive"))
      (node (ref "C28") (pin "1") (pinfunction "1_1") (pintype "passive"))
      (node (ref "C29") (pin "1") (pinfunction "1_1") (pintype "passive"))
      (node (ref "C30") (pin "1") (pinfunction "1_1") (pintype "passive"))
      (node (ref "C31") (pin "1") (pinfunction "1_1") (pintype "passive"))
      (node (ref "C32") (pin "1") (pinfunction "1_1") (pintype "passive"))
      (node (ref "C34") (pin "1") (pinfunction "1_1") (pintype "passive"))
      (node (ref "C35") (pin "1") (pinfunction "1_1") (pintype "passive"))
      (node (ref "C37") (pin "1") (pinfunction "1_1") (pintype "passive"))
      (node (ref "C38") (pin "1") (pinfunction "1_1") (pintype "passive"))
      (node (ref "C47") (pin "1") (pinfunction "1_1") (pintype "passive"))
      (node (ref "C48") (pin "1") (pinfunction "1_1") (pintype "passive"))
      (node (ref "C49") (pin "1") (pinfunction "1_1") (pintype "passive"))
      (node (ref "C50") (pin "1") (pinfunction "1_1") (pintype "passive"))
      (node (ref "C59") (pin "1") (pinfunction "1_1") (pintype "passive"))
      (node (ref "C62") (pin "1") (pinfunction "1_1") (pintype "passive"))
      (node (ref "C63") (pin "2") (pinfunction "2_2") (pintype "passive"))
      (node (ref "C64") (pin "1") (pinfunction "1_1") (pintype "passive"))
      (node (ref "C65") (pin "1") (pinfunction "1_1") (pintype "passive"))
      (node (ref "C66") (pin "1") (pinfunction "1_1") (pintype "passive"))
      (node (ref "C67") (pin "1") (pinfunction "1_1") (pintype "passive"))
      (node (ref "IC2") (pin "12") (pinfunction "GND_12") (pintype "power_in"))
      (node (ref "IC2") (pin "22") (pinfunction "GND_22") (pintype "power_in"))
      (node (ref "IC2") (pin "27") (pinfunction "GND_27") (pintype "power_in"))
      (node (ref "IC2") (pin "3") (pinfunction "GND_3") (pintype "power_in"))
      (node (ref "IC2") (pin "32") (pinfunction "GND_32") (pintype "power_in"))
      (node (ref "IC2") (pin "49") (pinfunction "GND_49") (pintype "power_in"))
      (node (ref "IC2") (pin "50") (pinfunction "GND_50") (pintype "power_in"))
      (node (ref "IC2") (pin "55") (pinfunction "GND_55") (pintype "power_in"))
      (node (ref "IC2") (pin "62") (pinfunction "GND_62") (pintype "power_in"))
      (node (ref "IC2") (pin "65") (pinfunction "EP_65") (pintype "power_in"))
      (node (ref "IC2") (pin "7") (pinfunction "GND_7") (pintype "power_in"))
      (node (ref "IC2") (pin "8") (pinfunction "GND_8") (pintype "power_in"))
      (node (ref "IC26") (pin "1") (pinfunction "GND_1") (pintype "power_in"))
      (node (ref "IC4") (pin "12") (pinfunction "GND_12") (pintype "passive"))
      (node (ref "IC4") (pin "14") (pinfunction "GND_14") (pintype "passive"))
      (node (ref "IC4") (pin "15") (pinfunction "GND_15") (pintype "passive"))
      (node (ref "IC4") (pin "9") (pinfunction "GND_9") (pintype "passive"))
      (node (ref "J10") (pin "2") (pinfunction "2_2") (pintype "bidirectional"))
      (node (ref "J12") (pin "2") (pinfunction "2_2") (pintype "bidirectional"))
      (node (ref "J13") (pin "2") (pinfunction "2_2") (pintype "bidirectional"))
      (node (ref "J7") (pin "2") (pinfunction "2_2") (pintype "bidirectional"))
      (node (ref "OSC2") (pin "3") (pinfunction "GND_3") (pintype "power_in"))
      (node (ref "R14") (pin "2") (pinfunction "2_2") (pintype "passive"))
      (node (ref "R15") (pin "2") (pinfunction "2_2") (pintype "passive"))
      (node (ref "R17") (pin "2") (pinfunction "2_2") (pintype "passive"))
      (node (ref "R18") (pin "2") (pinfunction "2_2") (pintype "passive"))
      (node (ref "R19") (pin "2") (pinfunction "2_2") (pintype "passive"))
      (node (ref "R20") (pin "2") (pinfunction "2_2") (pintype "passive"))
      (node (ref "R21") (pin "2") (pinfunction "2_2") (pintype "passive"))
      (node (ref "R23") (pin "2") (pinfunction "2_2") (pintype "passive"))
      (node (ref "R24") (pin "1") (pinfunction "1_1") (pintype "passive"))
      (node (ref "R29") (pin "2") (pinfunction "2_2") (pintype "passive"))
      (node (ref "R30") (pin "2") (pinfunction "2_2") (pintype "passive"))
      (node (ref "R31") (pin "2") (pinfunction "2_2") (pintype "passive"))
      (node (ref "R36") (pin "2") (pinfunction "2_2") (pintype "passive"))
      (node (ref "R37") (pin "2") (pinfunction "2_2") (pintype "passive"))
      (node (ref "R44") (pin "2") (pinfunction "2_2") (pintype "passive"))
      (node (ref "R7") (pin "2") (pinfunction "2_2") (pintype "passive"))
    )
    (net (code "45") (name "Net-(C14-Pad2)") (class "Default")
      (node (ref "C14") (pin "2") (pinfunction "2_2") (pintype "passive"))
      (node (ref "L10") (pin "3") (pinfunction "3_3") (pintype "passive"))
    )
    (net (code "46") (name "Net-(C61-Pad2)") (class "Default")
      (node (ref "C61") (pin "2") (pinfunction "2_2") (pintype "passive"))
      (node (ref "L10") (pin "1") (pinfunction "1_1") (pintype "passive"))
    )
    (net (code "47") (name "Net-(C65-Pad2)") (class "Default")
      (node (ref "C65") (pin "2") (pinfunction "2_2") (pintype "passive"))
      (node (ref "R40") (pin "2") (pinfunction "2_2") (pintype "passive"))
      (node (ref "R64") (pin "1") (pinfunction "1_1") (pintype "passive"))
    )
    (net (code "48") (name "Net-(C67-Pad2)") (class "Default")
      (node (ref "C67") (pin "2") (pinfunction "2_2") (pintype "passive"))
      (node (ref "R42") (pin "1") (pinfunction "1_1") (pintype "passive"))
    )
    (net (code "49") (name "Net-(IC2-CP)") (class "Default")
      (node (ref "C64") (pin "2") (pinfunction "2_2") (pintype "passive"))
      (node (ref "IC2") (pin "6") (pinfunction "CP_6") (pintype "output"))
      (node (ref "R40") (pin "1") (pinfunction "1_1") (pintype "passive"))
      (node (ref "R42") (pin "2") (pinfunction "2_2") (pintype "passive"))
    )
    (net (code "50") (name "Net-(IC2-CPRSET)") (class "Default")
      (node (ref "IC2") (pin "63") (pinfunction "CPRSET_63") (pintype "input"))
      (node (ref "R29") (pin "1") (pinfunction "1_1") (pintype "passive"))
    )
    (net (code "51") (name "Net-(IC2-RSET)") (class "Default")
      (node (ref "IC2") (pin "61") (pinfunction "RSET_61") (pintype "input"))
      (node (ref "R30") (pin "1") (pinfunction "1_1") (pintype "passive"))
    )
    (net (code "52") (name "Net-(IC26-EN)") (class "Default")
      (node (ref "IC26") (pin "8") (pinfunction "EN_8") (pintype "input"))
      (node (ref "R55") (pin "2") (pinfunction "2_2") (pintype "passive"))
    )
    (net (code "53") (name "Net-(IC26-SCL2)") (class "Default")
      (node (ref "IC26") (pin "6") (pinfunction "SCL2_6") (pintype "bidirectional"))
      (node (ref "OSC2") (pin "8") (pinfunction "SCL_8") (pintype "input"))
      (node (ref "R13") (pin "1") (pinfunction "1_1") (pintype "passive"))
    )
    (net (code "54") (name "Net-(IC26-SDA2)") (class "Default")
      (node (ref "IC26") (pin "5") (pinfunction "SDA2_5") (pintype "bidirectional"))
      (node (ref "OSC2") (pin "7") (pinfunction "SDA_7") (pintype "bidirectional"))
      (node (ref "R12") (pin "1") (pinfunction "1_1") (pintype "passive"))
    )
    (net (code "55") (name "Net-(J3-Pad1)") (class "Default")
      (node (ref "J3") (pin "1") (pinfunction "1_1") (pintype "bidirectional"))
      (node (ref "L3") (pin "4") (pinfunction "4_4") (pintype "passive"))
    )
    (net (code "56") (name "Net-(J3-Pad2)") (class "Default")
      (node (ref "J3") (pin "2") (pinfunction "2_2") (pintype "bidirectional"))
      (node (ref "L3") (pin "5") (pinfunction "5_5") (pintype "passive"))
      (node (ref "R24") (pin "2") (pinfunction "2_2") (pintype "passive"))
    )
    (net (code "57") (name "Net-(J4-Pad1)") (class "Default")
      (node (ref "J4") (pin "1") (pinfunction "1_1") (pintype "bidirectional"))
      (node (ref "L10") (pin "5") (pinfunction "5_5") (pintype "passive"))
      (node (ref "R28") (pin "1") (pinfunction "1_1") (pintype "passive"))
    )
    (net (code "58") (name "Net-(J4-Pad2)") (class "Default")
      (node (ref "J4") (pin "2") (pinfunction "2_2") (pintype "bidirectional"))
      (node (ref "L10") (pin "4") (pinfunction "4_4") (pintype "passive"))
      (node (ref "R28") (pin "2") (pinfunction "2_2") (pintype "passive"))
      (node (ref "R37") (pin "1") (pinfunction "1_1") (pintype "passive"))
    )
    (net (code "59") (name "Net-(OSC2-VDD)") (class "Default")
      (node (ref "C59") (pin "2") (pinfunction "2_2") (pintype "passive"))
      (node (ref "C63") (pin "1") (pinfunction "1_1") (pintype "passive"))
      (node (ref "L9") (pin "1") (pinfunction "1_1") (pintype "passive"))
      (node (ref "OSC2") (pin "6") (pinfunction "VDD_6") (pintype "power_in"))
    )
    (net (code "60") (name "Net-(OSC2-Vc)") (class "Default")
      (node (ref "C66") (pin "2") (pinfunction "2_2") (pintype "passive"))
      (node (ref "OSC2") (pin "1") (pinfunction "Vc_1") (pintype "input"))
      (node (ref "R64") (pin "2") (pinfunction "2_2") (pintype "passive"))
    )
    (net (code "61") (name "Net-(R22-Pad2)") (class "Default")
      (node (ref "R22") (pin "2") (pinfunction "2_2") (pintype "passive"))
      (node (ref "R25") (pin "2") (pinfunction "2_2") (pintype "passive"))
      (node (ref "R5") (pin "2") (pinfunction "2_2") (pintype "passive"))
      (node (ref "R54") (pin "2") (pinfunction "2_2") (pintype "passive"))
      (node (ref "R56") (pin "2") (pinfunction "2_2") (pintype "passive"))
      (node (ref "R7") (pin "1") (pinfunction "1_1") (pintype "passive"))
    )
    (net (code "62") (name "P3V3CLK") (class "Default")
      (node (ref "C26") (pin "2") (pinfunction "2_2") (pintype "passive"))
      (node (ref "C27") (pin "2") (pinfunction "2_2") (pintype "passive"))
      (node (ref "C28") (pin "2") (pinfunction "2_2") (pintype "passive"))
      (node (ref "C29") (pin "2") (pinfunction "2_2") (pintype "passive"))
      (node (ref "C30") (pin "2") (pinfunction "2_2") (pintype "passive"))
      (node (ref "C31") (pin "2") (pinfunction "2_2") (pintype "passive"))
      (node (ref "C32") (pin "2") (pinfunction "2_2") (pintype "passive"))
      (node (ref "C34") (pin "2") (pinfunction "2_2") (pintype "passive"))
      (node (ref "C35") (pin "2") (pinfunction "2_2") (pintype "passive"))
      (node (ref "C37") (pin "2") (pinfunction "2_2") (pintype "passive"))
      (node (ref "C38") (pin "2") (pinfunction "2_2") (pintype "passive"))
      (node (ref "C47") (pin "2") (pinfunction "2_2") (pintype "passive"))
      (node (ref "C48") (pin "2") (pinfunction "2_2") (pintype "passive"))
      (node (ref "C49") (pin "2") (pinfunction "2_2") (pintype "passive"))
      (node (ref "C50") (pin "2") (pinfunction "2_2") (pintype "passive"))
      (node (ref "C62") (pin "2") (pinfunction "2_2") (pintype "passive"))
      (node (ref "IC2") (pin "13") (pinfunction "VS_13") (pintype "power_in"))
      (node (ref "IC2") (pin "23") (pinfunction "VS_23") (pintype "power_in"))
      (node (ref "IC2") (pin "26") (pinfunction "VS_26") (pintype "power_in"))
      (node (ref "IC2") (pin "30") (pinfunction "VS_30") (pintype "power_in"))
      (node (ref "IC2") (pin "31") (pinfunction "VS_31") (pintype "power_in"))
      (node (ref "IC2") (pin "33") (pinfunction "VS_33") (pintype "power_in"))
      (node (ref "IC2") (pin "36") (pinfunction "VS_36") (pintype "power_in"))
      (node (ref "IC2") (pin "37") (pinfunction "VS_37") (pintype "power_in"))
      (node (ref "IC2") (pin "4") (pinfunction "VS_4") (pintype "power_in"))
      (node (ref "IC2") (pin "40") (pinfunction "VS_40") (pintype "power_in"))
      (node (ref "IC2") (pin "41") (pinfunction "VS_41") (pintype "power_in"))
      (node (ref "IC2") (pin "44") (pinfunction "VS_44") (pintype "power_in"))
      (node (ref "IC2") (pin "45") (pinfunction "VS_45") (pintype "power_in"))
      (node (ref "IC2") (pin "48") (pinfunction "VS_48") (pintype "power_in"))
      (node (ref "IC2") (pin "5") (pinfunction "VCP_5") (pintype "power_in"))
      (node (ref "IC2") (pin "51") (pinfunction "VS_51") (pintype "power_in"))
      (node (ref "IC2") (pin "52") (pinfunction "VS_52") (pintype "power_in"))
      (node (ref "IC2") (pin "56") (pinfunction "VS_56") (pintype "power_in"))
      (node (ref "IC2") (pin "59") (pinfunction "VS_59") (pintype "power_in"))
      (node (ref "IC2") (pin "60") (pinfunction "VS_60") (pintype "power_in"))
      (node (ref "IC2") (pin "64") (pinfunction "VS_64") (pintype "power_in"))
      (node (ref "IC2") (pin "9") (pinfunction "VS_9") (pintype "power_in"))
      (node (ref "IC26") (pin "7") (pinfunction "VREF2_7") (pintype "input"))
      (node (ref "IC4") (pin "13") (pinfunction "Vdd_13") (pintype "power_in"))
      (node (ref "IC4") (pin "8") (pinfunction "Vdd_8") (pintype "power_in"))
      (node (ref "L9") (pin "2") (pinfunction "2_2") (pintype "passive"))
      (node (ref "R12") (pin "2") (pinfunction "2_2") (pintype "passive"))
      (node (ref "R13") (pin "2") (pinfunction "2_2") (pintype "passive"))
      (node (ref "R5") (pin "1") (pinfunction "1_1") (pintype "passive"))
      (node (ref "R55") (pin "1") (pinfunction "1_1") (pintype "passive"))
    )
    (net (code "63") (name "VADJ") (class "Default")
      (node (ref "IC26") (pin "2") (pinfunction "VREF1_2") (pintype "input"))
    )
    (net (code "64") (name "unconnected-(IC2-OUT5-Pad43)") (class "Default")
      (node (ref "IC2") (pin "43") (pinfunction "OUT5_43") (pintype "output"))
    )
    (net (code "65") (name "unconnected-(IC2-OUT5B-Pad42)") (class "Default")
      (node (ref "IC2") (pin "42") (pinfunction "OUT5B_42") (pintype "output"))
    )
    (net (code "66") (name "unconnected-(IC2-OUT6-Pad39)") (class "Default")
      (node (ref "IC2") (pin "39") (pinfunction "OUT6_39") (pintype "output"))
    )
    (net (code "67") (name "unconnected-(IC2-OUT6B-Pad38)") (class "Default")
      (node (ref "IC2") (pin "38") (pinfunction "OUT6B_38") (pintype "output"))
    )
    (net (code "68") (name "unconnected-(IC4-nc-Pad7)") (class "Default")
      (node (ref "IC4") (pin "7") (pinfunction "nc_7") (pintype "passive"))
    )
    (net (code "69") (name "unconnected-(IC4-nc-Pad16)") (class "Default")
      (node (ref "IC4") (pin "16") (pinfunction "nc_16") (pintype "passive"))
    )
    (net (code "70") (name "unconnected-(IC4-reserved-Pad5)") (class "Default")
      (node (ref "IC4") (pin "5") (pinfunction "reserved_5") (pintype "passive"))
    )
  )
)
